# Buttons.net
KiCad netlist of a schematic drawn in Altium Designer
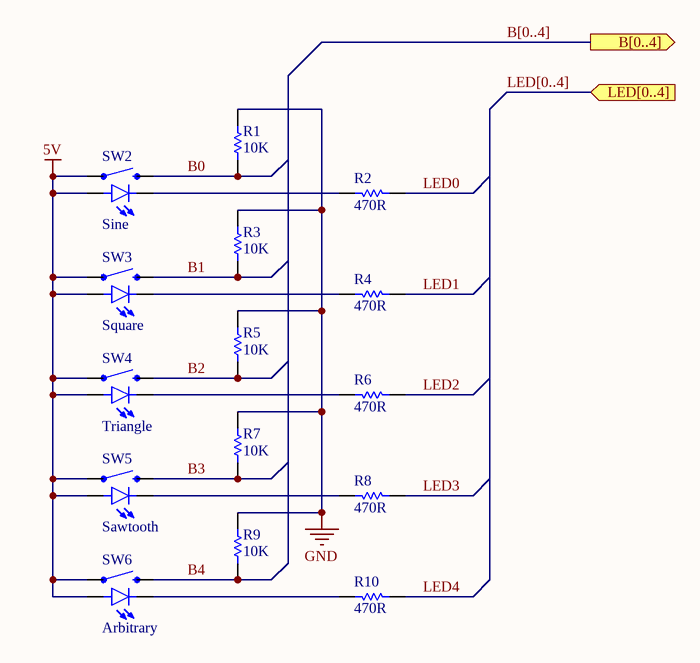
[diagram p0: Buttons.SchDoc]

(export (version "E")
  (design (tool "Eeschema 10.0.6"))
  (components
    (comp (ref "R1") (value "10K") (footprint "RESISTOR") (libsource (lib "Components") (part "Resistor")))
    (comp (ref "R2") (value "470R") (footprint "RESISTOR") (libsource (lib "Components") (part "Resistor")))
    (comp (ref "R3") (value "10K") (footprint "RESISTOR") (libsource (lib "Components") (part "Resistor")))
    (comp (ref "R4") (value "470R") (footprint "RESISTOR") (libsource (lib "Components") (part "Resistor")))
    (comp (ref "R5") (value "10K") (footprint "RESISTOR") (libsource (lib "Components") (part "Resistor")))
    (comp (ref "R6") (value "470R") (footprint "RESISTOR") (libsource (lib "Components") (part "Resistor")))
    (comp (ref "R7") (value "10K") (footprint "RESISTOR") (libsource (lib "Components") (part "Resistor")))
    (comp (ref "R8") (value "470R") (footprint "RESISTOR") (libsource (lib "Components") (part "Resistor")))
    (comp (ref "R9") (value "10K") (footprint "RESISTOR") (libsource (lib "Components") (part "Resistor")))
    (comp (ref "R10") (value "470R") (footprint "RESISTOR") (libsource (lib "Components") (part "Resistor")))
    (comp (ref "SW2")
      (value "Sine")
      (footprint "TACTILE-PTH-LED")
      (libsource (lib "Components") (part "SwitchLED"))
    )
    (comp (ref "SW3")
      (value "Square")
      (footprint "TACTILE-PTH-LED")
      (libsource (lib "Components") (part "SwitchLED"))
    )
    (comp (ref "SW4")
      (value "Triangle")
      (footprint "TACTILE-PTH-LED")
      (libsource (lib "Components") (part "SwitchLED"))
    )
    (comp (ref "SW5")
      (value "Sawtooth")
      (footprint "TACTILE-PTH-LED")
      (libsource (lib "Components") (part "SwitchLED"))
    )
    (comp (ref "SW6")
      (value "Arbitrary")
      (footprint "TACTILE-PTH-LED")
      (libsource (lib "Components") (part "SwitchLED"))
    )
  )
  (nets
    (net (code "1") (name "/B0") (class "Default")
      (node (ref "R1") (pin "2") (pinfunction "2_2") (pintype "passive"))
      (node (ref "SW2") (pin "2") (pinfunction "2_2") (pintype "passive"))
    )
    (net (code "2") (name "/B1") (class "Default")
      (node (ref "R3") (pin "2") (pinfunction "2_2") (pintype "passive"))
      (node (ref "SW3") (pin "2") (pinfunction "2_2") (pintype "passive"))
    )
    (net (code "3") (name "/B2") (class "Default")
      (node (ref "R5") (pin "2") (pinfunction "2_2") (pintype "passive"))
      (node (ref "SW4") (pin "2") (pinfunction "2_2") (pintype "passive"))
    )
    (net (code "4") (name "/B3") (class "Default")
      (node (ref "R7") (pin "2") (pinfunction "2_2") (pintype "passive"))
      (node (ref "SW5") (pin "2") (pinfunction "2_2") (pintype "passive"))
    )
    (net (code "5") (name "/B4") (class "Default")
      (node (ref "R9") (pin "2") (pinfunction "2_2") (pintype "passive"))
      (node (ref "SW6") (pin "2") (pinfunction "2_2") (pintype "passive"))
    )
    (net (code "7") (name "/LED0") (class "Default")
      (node (ref "R2") (pin "1") (pinfunction "1_1") (pintype "passive"))
    )
    (net (code "8") (name "/LED1") (class "Default")
      (node (ref "R4") (pin "1") (pinfunction "1_1") (pintype "passive"))
    )
    (net (code "9") (name "/LED2") (class "Default")
      (node (ref "R6") (pin "1") (pinfunction "1_1") (pintype "passive"))
    )
    (net (code "10") (name "/LED3") (class "Default")
      (node (ref "R8") (pin "1") (pinfunction "1_1") (pintype "passive"))
    )
    (net (code "11") (name "/LED4") (class "Default")
      (node (ref "R10") (pin "1") (pinfunction "1_1") (pintype "passive"))
    )
    (net (code "13") (name "5V") (class "Default")
      (node (ref "SW2") (pin "4") (pinfunction "1_4") (pintype "passive"))
      (node (ref "SW2") (pin "A") (pinfunction "A_A") (pintype "passive"))
      (node (ref "SW3") (pin "4") (pinfunction "1_4") (pintype "passive"))
      (node (ref "SW3") (pin "A") (pinfunction "A_A") (pintype "passive"))
      (node (ref "SW4") (pin "4") (pinfunction "1_4") (pintype "passive"))
      (node (ref "SW4") (pin "A") (pinfunction "A_A") (pintype "passive"))
      (node (ref "SW5") (pin "4") (pinfunction "1_4") (pintype "passive"))
      (node (ref "SW5") (pin "A") (pinfunction "A_A") (pintype "passive"))
      (node (ref "SW6") (pin "4") (pinfunction "1_4") (pintype "passive"))
      (node (ref "SW6") (pin "A") (pinfunction "A_A") (pintype "passive"))
    )
    (net (code "14") (name "GND") (class "Default")
      (node (ref "R1") (pin "1") (pinfunction "1_1") (pintype "passive"))
      (node (ref "R3") (pin "1") (pinfunction "1_1") (pintype "passive"))
      (node (ref "R5") (pin "1") (pinfunction "1_1") (pintype "passive"))
      (node (ref "R7") (pin "1") (pinfunction "1_1") (pintype "passive"))
      (node (ref "R9") (pin "1") (pinfunction "1_1") (pintype "passive"))
    )
    (net (code "15") (name "Net-(R2-Pad2)") (class "Default")
      (node (ref "R2") (pin "2") (pinfunction "2_2") (pintype "passive"))
      (node (ref "SW2") (pin "C") (pinfunction "C_C") (pintype "passive"))
    )
    (net (code "16") (name "Net-(R4-Pad2)") (class "Default")
      (node (ref "R4") (pin "2") (pinfunction "2_2") (pintype "passive"))
      (node (ref "SW3") (pin "C") (pinfunction "C_C") (pintype "passive"))
    )
    (net (code "17") (name "Net-(R6-Pad2)") (class "Default")
      (node (ref "R6") (pin "2") (pinfunction "2_2") (pintype "passive"))
      (node (ref "SW4") (pin "C") (pinfunction "C_C") (pintype "passive"))
    )
    (net (code "18") (name "Net-(R8-Pad2)") (class "Default")
      (node (ref "R8") (pin "2") (pinfunction "2_2") (pintype "passive"))
      (node (ref "SW5") (pin "C") (pinfunction "C_C") (pintype "passive"))
    )
    (net (code "19") (name "Net-(R10-Pad2)") (class "Default")
      (node (ref "R10") (pin "2") (pinfunction "2_2") (pintype "passive"))
      (node (ref "SW6") (pin "C") (pinfunction "C_C") (pintype "passive"))
    )
  )
)
